# Key.net
KiCad netlist of a schematic drawn in Altium Designer
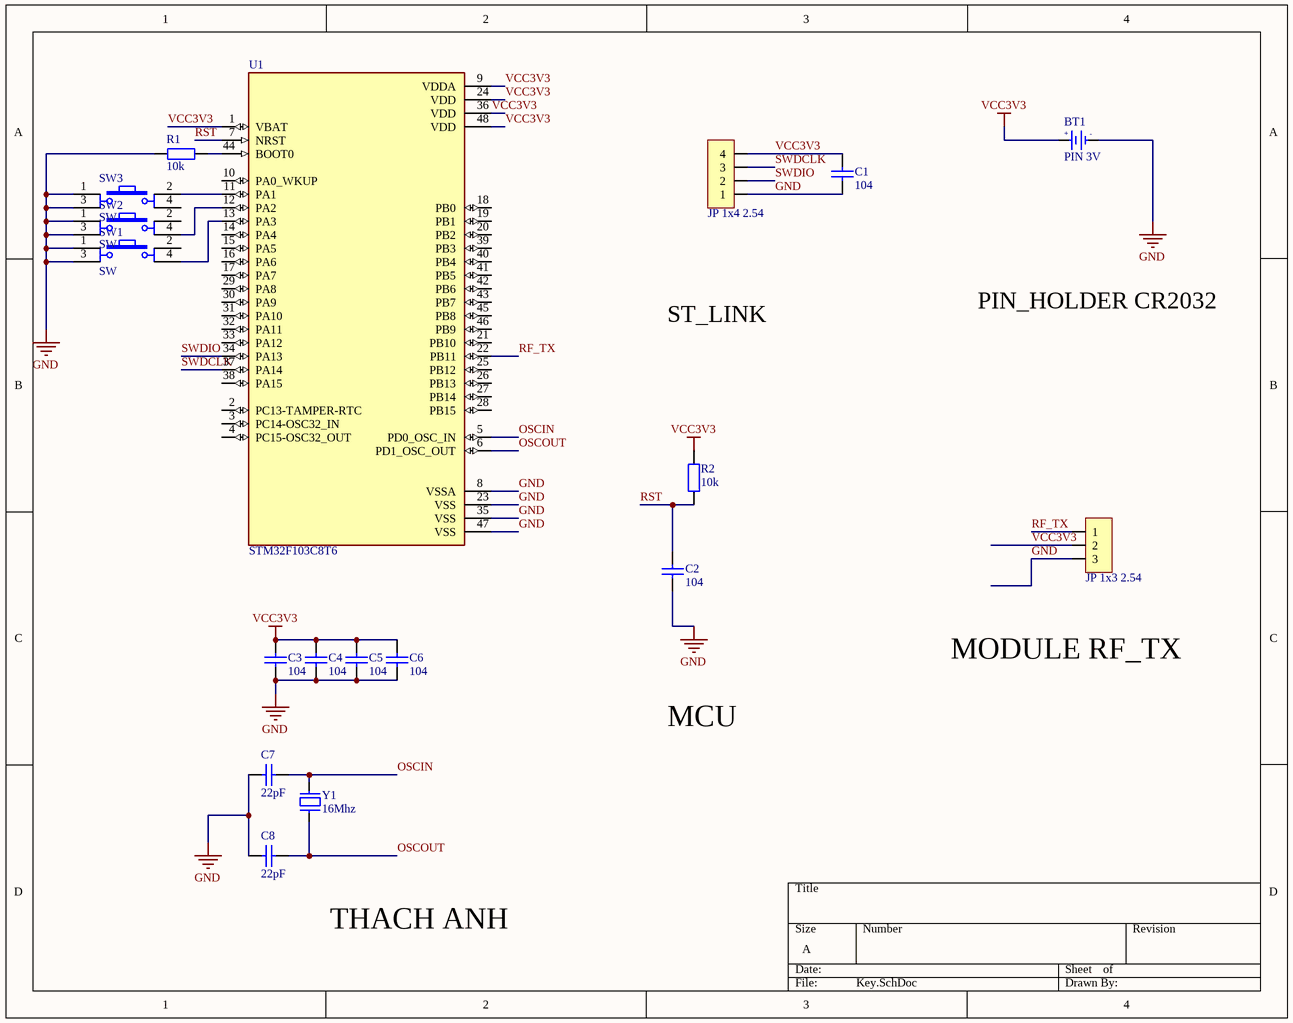
[diagram p0: Key.SchDoc]

(export (version "E")
  (design (tool "Eeschema 10.0.6"))
  (components
    (comp (ref "BT1")
      (value "PIN 3V")
      (footprint "PIN3V")
      (description "Battery 3VDC")
      (libsource (lib "Cty1") (part "PIN 3V"))
    )
    (comp (ref "C1")
      (value "104")
      (footprint "tu 0805")
      (description "Dán")
      (libsource (lib "Altium_Lib_by_KhueNguyenCreator") (part "Tu 0805 104 50V 10%"))
    )
    (comp (ref "C2")
      (value "104")
      (footprint "tu 0805")
      (description "Dán")
      (libsource (lib "Altium_Lib_by_KhueNguyenCreator") (part "Tu 0805 104 50V 10%"))
    )
    (comp (ref "C3")
      (value "104")
      (footprint "tu 0805")
      (description "Dán")
      (libsource (lib "Altium_Lib_by_KhueNguyenCreator") (part "Tu 0805 104 50V 10%"))
    )
    (comp (ref "C4")
      (value "104")
      (footprint "tu 0805")
      (description "Dán")
      (libsource (lib "Altium_Lib_by_KhueNguyenCreator") (part "Tu 0805 104 50V 10%"))
    )
    (comp (ref "C5")
      (value "104")
      (footprint "tu 0805")
      (description "Dán")
      (libsource (lib "Altium_Lib_by_KhueNguyenCreator") (part "Tu 0805 104 50V 10%"))
    )
    (comp (ref "C6")
      (value "104")
      (footprint "tu 0805")
      (description "Dán")
      (libsource (lib "Altium_Lib_by_KhueNguyenCreator") (part "Tu 0805 104 50V 10%"))
    )
    (comp (ref "C7")
      (value "22pF")
      (footprint "tu 0805")
      (description "Dán")
      (libsource (lib "Altium_Lib_by_KhueNguyenCreator") (part "Tu 0805 22pF 50V 10%"))
    )
    (comp (ref "C8")
      (value "22pF")
      (footprint "tu 0805")
      (description "Dán")
      (libsource (lib "Altium_Lib_by_KhueNguyenCreator") (part "Tu 0805 22pF 50V 10%"))
    )
    (comp (ref "JP1")
      (value "JP 1x4 2.54")
      (footprint "JP 1x4 DT")
      (description "Cắm")
      (libsource (lib "Altium_Lib_by_KhueNguyenCreator") (part "JP 1x4 2.54 Duc Thang"))
    )
    (comp (ref "JP2")
      (value "JP 1x3 2.54")
      (footprint "JP 1x3 CT")
      (description "Cắm")
      (libsource (lib "Altium_Lib_by_KhueNguyenCreator") (part "JP 1x3 2.54 Cai Thang"))
    )
    (comp (ref "R1")
      (value "10k")
      (footprint "tro smd 0603")
      (description "Dán")
      (libsource (lib "Altium_Lib_by_KhueNguyenCreator") (part "Tro 0603 5% 10k"))
    )
    (comp (ref "R2")
      (value "10k")
      (footprint "tro smd 0603")
      (description "Dán")
      (libsource (lib "Altium_Lib_by_KhueNguyenCreator") (part "Tro 0603 5% 10k"))
    )
    (comp (ref "SW1")
      (value "SW")
      (footprint "SW4")
      (description "Switch button 4 pin")
      (libsource (lib "syhaunguyen") (part "SW4"))
    )
    (comp (ref "SW2")
      (value "SW")
      (footprint "SW4")
      (description "Switch button 4 pin")
      (libsource (lib "syhaunguyen") (part "SW4"))
    )
    (comp (ref "SW3")
      (value "SW")
      (footprint "SW4")
      (description "Switch button 4 pin")
      (libsource (lib "syhaunguyen") (part "SW4"))
    )
    (comp (ref "U1")
      (value "STM32F103C8T6")
      (footprint "QFP50P900X900X160-48N")
      (description "ARMÂ® CortexÂ®-M3 STM32F1 Microcontroller IC 32-Bit 72MHz 64KB _64K x 8_ FLASH")
      (fields (field (name "MF") "STMicroelectronics"))
      (libsource (lib "STM32F103C8T6") (part "STM32F103C8T6"))
    )
    (comp (ref "Y1")
      (value "16Mhz")
      (footprint "Thach Anh 2 chan cam")
      (description "Crystal For all Crystal 2pin.")
      (libsource (lib "Altium_Lib_by_KhueNguyenCreator") (part "Thach Anh 2 chan Cam"))
    )
  )
  (nets
    (net (code "1") (name "/OSCIN") (class "Default")
      (node (ref "C7") (pin "1") (pinfunction "1_1") (pintype "passive"))
      (node (ref "U1") (pin "5") (pinfunction "PD0_OSC_IN_5") (pintype "bidirectional"))
      (node (ref "Y1") (pin "2") (pinfunction "2_2") (pintype "passive"))
    )
    (net (code "2") (name "/OSCOUT") (class "Default")
      (node (ref "C8") (pin "1") (pinfunction "1_1") (pintype "passive"))
      (node (ref "U1") (pin "6") (pinfunction "PD1_OSC_OUT_6") (pintype "bidirectional"))
      (node (ref "Y1") (pin "1") (pinfunction "1_1") (pintype "passive"))
    )
    (net (code "3") (name "/RF_TX") (class "Default")
      (node (ref "JP2") (pin "1") (pinfunction "1_1") (pintype "passive"))
      (node (ref "U1") (pin "22") (pinfunction "PB11_22") (pintype "bidirectional"))
    )
    (net (code "4") (name "/RST") (class "Default")
      (node (ref "C2") (pin "1") (pinfunction "1_1") (pintype "passive"))
      (node (ref "R2") (pin "1") (pinfunction "1_1") (pintype "passive"))
      (node (ref "U1") (pin "7") (pinfunction "NRST_7") (pintype "input"))
    )
    (net (code "5") (name "/SWDCLK") (class "Default")
      (node (ref "JP1") (pin "3") (pinfunction "3_3") (pintype "passive"))
      (node (ref "U1") (pin "37") (pinfunction "PA14_37") (pintype "bidirectional"))
    )
    (net (code "6") (name "/SWDIO") (class "Default")
      (node (ref "JP1") (pin "2") (pinfunction "2_2") (pintype "passive"))
      (node (ref "U1") (pin "34") (pinfunction "PA13_34") (pintype "bidirectional"))
    )
    (net (code "7") (name "GND") (class "Default")
      (node (ref "BT1") (pin "2") (pinfunction "GND_2") (pintype "passive"))
      (node (ref "C1") (pin "2") (pinfunction "2_2") (pintype "passive"))
      (node (ref "C2") (pin "2") (pinfunction "2_2") (pintype "passive"))
      (node (ref "C3") (pin "2") (pinfunction "2_2") (pintype "passive"))
      (node (ref "C4") (pin "2") (pinfunction "2_2") (pintype "passive"))
      (node (ref "C5") (pin "2") (pinfunction "2_2") (pintype "passive"))
      (node (ref "C6") (pin "2") (pinfunction "2_2") (pintype "passive"))
      (node (ref "C7") (pin "2") (pinfunction "2_2") (pintype "passive"))
      (node (ref "C8") (pin "2") (pinfunction "2_2") (pintype "passive"))
      (node (ref "JP1") (pin "1") (pinfunction "1_1") (pintype "passive"))
      (node (ref "JP2") (pin "3") (pinfunction "3_3") (pintype "passive"))
      (node (ref "R1") (pin "2") (pinfunction "2_2") (pintype "passive"))
      (node (ref "SW1") (pin "1") (pintype "passive"))
      (node (ref "SW1") (pin "3") (pintype "passive"))
      (node (ref "SW2") (pin "1") (pintype "passive"))
      (node (ref "SW2") (pin "3") (pintype "passive"))
      (node (ref "SW3") (pin "1") (pintype "passive"))
      (node (ref "SW3") (pin "3") (pintype "passive"))
      (node (ref "U1") (pin "23") (pinfunction "VSS_23") (pintype "power_in"))
      (node (ref "U1") (pin "35") (pinfunction "VSS_35") (pintype "power_in"))
      (node (ref "U1") (pin "47") (pinfunction "VSS_47") (pintype "power_in"))
      (node (ref "U1") (pin "8") (pinfunction "VSSA_8") (pintype "power_in"))
    )
    (net (code "8") (name "Net-(U1-BOOT0)") (class "Default")
      (node (ref "R1") (pin "1") (pinfunction "1_1") (pintype "passive"))
      (node (ref "U1") (pin "44") (pinfunction "BOOT0_44") (pintype "input"))
    )
    (net (code "9") (name "Net-(U1-PA1)") (class "Default")
      (node (ref "SW3") (pin "2") (pintype "passive"))
      (node (ref "U1") (pin "11") (pinfunction "PA1_11") (pintype "bidirectional"))
    )
    (net (code "10") (name "Net-(U1-PA2)") (class "Default")
      (node (ref "SW2") (pin "4") (pintype "passive"))
      (node (ref "U1") (pin "12") (pinfunction "PA2_12") (pintype "bidirectional"))
    )
    (net (code "11") (name "Net-(U1-PA3)") (class "Default")
      (node (ref "SW1") (pin "4") (pintype "passive"))
      (node (ref "U1") (pin "13") (pinfunction "PA3_13") (pintype "bidirectional"))
    )
    (net (code "12") (name "VCC3V3") (class "Default")
      (node (ref "BT1") (pin "1") (pinfunction "+3V_1") (pintype "passive"))
      (node (ref "C1") (pin "1") (pinfunction "1_1") (pintype "passive"))
      (node (ref "C3") (pin "1") (pinfunction "1_1") (pintype "passive"))
      (node (ref "C4") (pin "1") (pinfunction "1_1") (pintype "passive"))
      (node (ref "C5") (pin "1") (pinfunction "1_1") (pintype "passive"))
      (node (ref "C6") (pin "1") (pinfunction "1_1") (pintype "passive"))
      (node (ref "JP1") (pin "4") (pinfunction "4_4") (pintype "passive"))
      (node (ref "JP2") (pin "2") (pinfunction "2_2") (pintype "passive"))
      (node (ref "R2") (pin "2") (pinfunction "2_2") (pintype "passive"))
      (node (ref "U1") (pin "1") (pinfunction "VBAT_1") (pintype "bidirectional"))
      (node (ref "U1") (pin "24") (pinfunction "VDD_24") (pintype "power_in"))
      (node (ref "U1") (pin "36") (pinfunction "VDD_36") (pintype "power_in"))
      (node (ref "U1") (pin "48") (pinfunction "VDD_48") (pintype "power_in"))
      (node (ref "U1") (pin "9") (pinfunction "VDDA_9") (pintype "power_in"))
    )
    (net (code "13") (name "unconnected-(SW1-Pad2)") (class "Default")
      (node (ref "SW1") (pin "2") (pintype "passive"))
    )
    (net (code "14") (name "unconnected-(SW2-Pad2)") (class "Default")
      (node (ref "SW2") (pin "2") (pintype "passive"))
    )
    (net (code "15") (name "unconnected-(SW3-Pad4)") (class "Default")
      (node (ref "SW3") (pin "4") (pintype "passive"))
    )
    (net (code "16") (name "unconnected-(U1-PA0_WKUP-Pad10)") (class "Default")
      (node (ref "U1") (pin "10") (pinfunction "PA0_WKUP_10") (pintype "bidirectional"))
    )
    (net (code "17") (name "unconnected-(U1-PA4-Pad14)") (class "Default")
      (node (ref "U1") (pin "14") (pinfunction "PA4_14") (pintype "bidirectional"))
    )
    (net (code "18") (name "unconnected-(U1-PA5-Pad15)") (class "Default")
      (node (ref "U1") (pin "15") (pinfunction "PA5_15") (pintype "bidirectional"))
    )
    (net (code "19") (name "unconnected-(U1-PA6-Pad16)") (class "Default")
      (node (ref "U1") (pin "16") (pinfunction "PA6_16") (pintype "bidirectional"))
    )
    (net (code "20") (name "unconnected-(U1-PA7-Pad17)") (class "Default")
      (node (ref "U1") (pin "17") (pinfunction "PA7_17") (pintype "bidirectional"))
    )
    (net (code "21") (name "unconnected-(U1-PA8-Pad29)") (class "Default")
      (node (ref "U1") (pin "29") (pinfunction "PA8_29") (pintype "bidirectional"))
    )
    (net (code "22") (name "unconnected-(U1-PA9-Pad30)") (class "Default")
      (node (ref "U1") (pin "30") (pinfunction "PA9_30") (pintype "bidirectional"))
    )
    (net (code "23") (name "unconnected-(U1-PA10-Pad31)") (class "Default")
      (node (ref "U1") (pin "31") (pinfunction "PA10_31") (pintype "bidirectional"))
    )
    (net (code "24") (name "unconnected-(U1-PA11-Pad32)") (class "Default")
      (node (ref "U1") (pin "32") (pinfunction "PA11_32") (pintype "bidirectional"))
    )
    (net (code "25") (name "unconnected-(U1-PA12-Pad33)") (class "Default")
      (node (ref "U1") (pin "33") (pinfunction "PA12_33") (pintype "bidirectional"))
    )
    (net (code "26") (name "unconnected-(U1-PA15-Pad38)") (class "Default")
      (node (ref "U1") (pin "38") (pinfunction "PA15_38") (pintype "bidirectional"))
    )
    (net (code "27") (name "unconnected-(U1-PB0-Pad18)") (class "Default")
      (node (ref "U1") (pin "18") (pinfunction "PB0_18") (pintype "bidirectional"))
    )
    (net (code "28") (name "unconnected-(U1-PB1-Pad19)") (class "Default")
      (node (ref "U1") (pin "19") (pinfunction "PB1_19") (pintype "bidirectional"))
    )
    (net (code "29") (name "unconnected-(U1-PB2-Pad20)") (class "Default")
      (node (ref "U1") (pin "20") (pinfunction "PB2_20") (pintype "bidirectional"))
    )
    (net (code "30") (name "unconnected-(U1-PB3-Pad39)") (class "Default")
      (node (ref "U1") (pin "39") (pinfunction "PB3_39") (pintype "bidirectional"))
    )
    (net (code "31") (name "unconnected-(U1-PB4-Pad40)") (class "Default")
      (node (ref "U1") (pin "40") (pinfunction "PB4_40") (pintype "bidirectional"))
    )
    (net (code "32") (name "unconnected-(U1-PB5-Pad41)") (class "Default")
      (node (ref "U1") (pin "41") (pinfunction "PB5_41") (pintype "bidirectional"))
    )
    (net (code "33") (name "unconnected-(U1-PB6-Pad42)") (class "Default")
      (node (ref "U1") (pin "42") (pinfunction "PB6_42") (pintype "bidirectional"))
    )
    (net (code "34") (name "unconnected-(U1-PB7-Pad43)") (class "Default")
      (node (ref "U1") (pin "43") (pinfunction "PB7_43") (pintype "bidirectional"))
    )
    (net (code "35") (name "unconnected-(U1-PB8-Pad45)") (class "Default")
      (node (ref "U1") (pin "45") (pinfunction "PB8_45") (pintype "bidirectional"))
    )
    (net (code "36") (name "unconnected-(U1-PB9-Pad46)") (class "Default")
      (node (ref "U1") (pin "46") (pinfunction "PB9_46") (pintype "bidirectional"))
    )
    (net (code "37") (name "unconnected-(U1-PB10-Pad21)") (class "Default")
      (node (ref "U1") (pin "21") (pinfunction "PB10_21") (pintype "bidirectional"))
    )
    (net (code "38") (name "unconnected-(U1-PB12-Pad25)") (class "Default")
      (node (ref "U1") (pin "25") (pinfunction "PB12_25") (pintype "bidirectional"))
    )
    (net (code "39") (name "unconnected-(U1-PB13-Pad26)") (class "Default")
      (node (ref "U1") (pin "26") (pinfunction "PB13_26") (pintype "bidirectional"))
    )
    (net (code "40") (name "unconnected-(U1-PB14-Pad27)") (class "Default")
      (node (ref "U1") (pin "27") (pinfunction "PB14_27") (pintype "bidirectional"))
    )
    (net (code "41") (name "unconnected-(U1-PB15-Pad28)") (class "Default")
      (node (ref "U1") (pin "28") (pinfunction "PB15_28") (pintype "bidirectional"))
    )
    (net (code "42") (name "unconnected-(U1-PC13-TAMPER-RTC-Pad2)") (class "Default")
      (node (ref "U1") (pin "2") (pinfunction "PC13-TAMPER-RTC_2") (pintype "bidirectional"))
    )
    (net (code "43") (name "unconnected-(U1-PC14-OSC32_IN-Pad3)") (class "Default")
      (node (ref "U1") (pin "3") (pinfunction "PC14-OSC32_IN_3") (pintype "bidirectional"))
    )
    (net (code "44") (name "unconnected-(U1-PC15-OSC32_OUT-Pad4)") (class "Default")
      (node (ref "U1") (pin "4") (pinfunction "PC15-OSC32_OUT_4") (pintype "bidirectional"))
    )
  )
)
